# main1.net
KiCad netlist of a schematic drawn in EAGLE
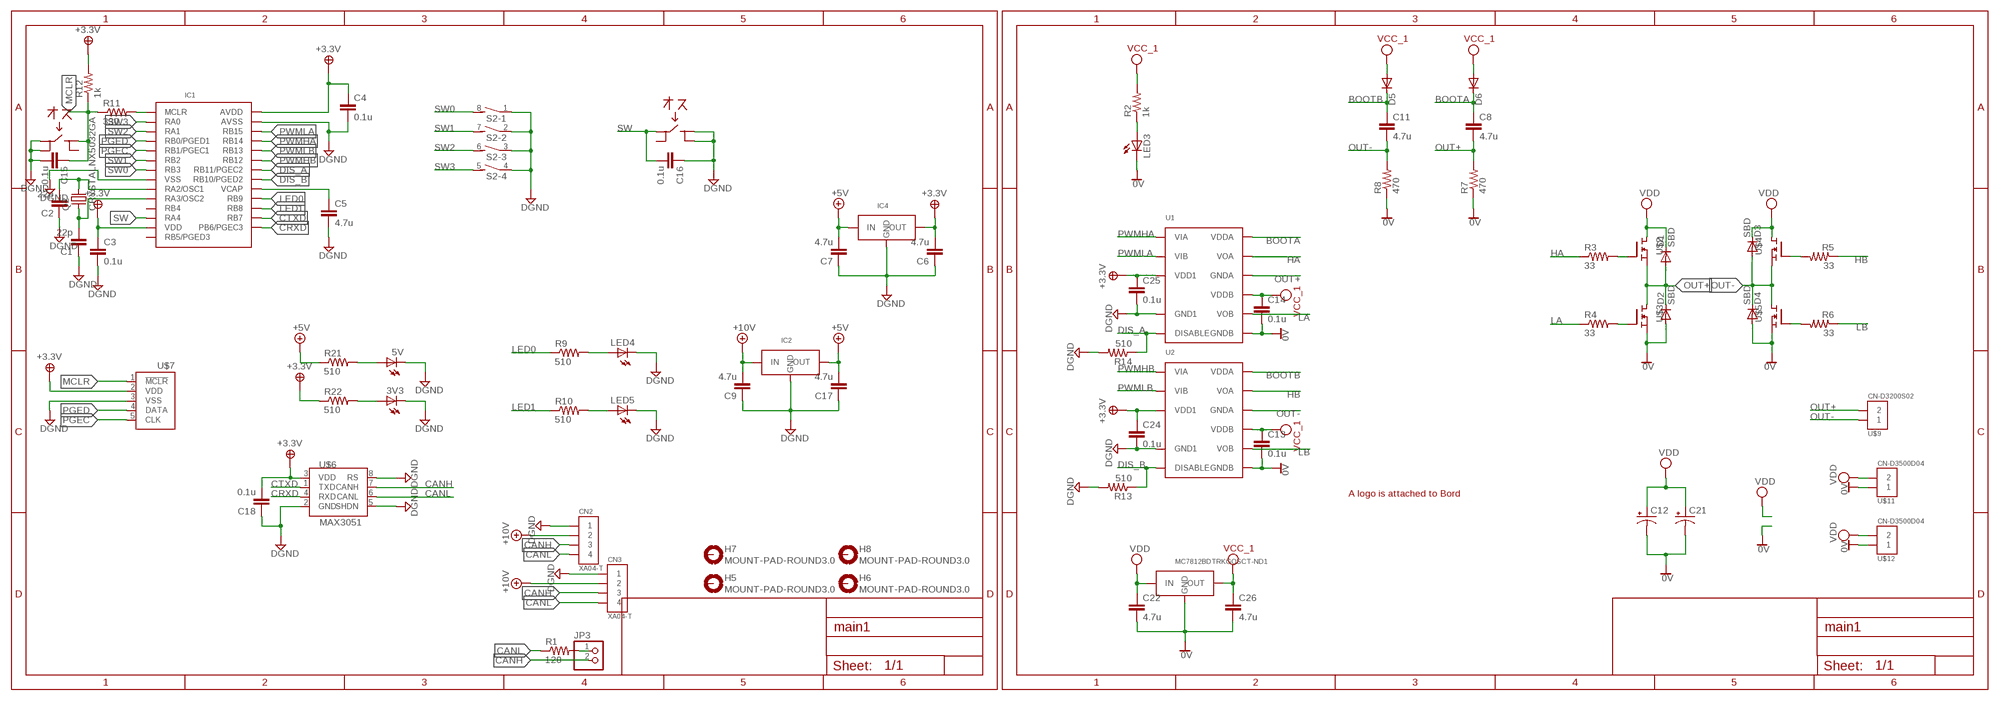
[diagram p0: schematic, sheet 1]

(export (version "E")
  (design (tool "Eeschema 10.0.6"))
  (components
    (comp (ref "3V3")
      (value "LEDCHIPLED_0805")
      (footprint "eagle-import:CHIPLED_0805")
      (libsource (lib "eagle-import") (part "LEDCHIPLED_0805"))
    )
    (comp (ref "5V")
      (value "LEDCHIPLED_0805")
      (footprint "eagle-import:CHIPLED_0805")
      (libsource (lib "eagle-import") (part "LEDCHIPLED_0805"))
    )
    (comp (ref "C1")
      (value "22p")
      (footprint "eagle-import:C0603K")
      (libsource (lib "eagle-import") (part "C-EUC0603K"))
    )
    (comp (ref "C2")
      (value "22p")
      (footprint "eagle-import:C0603K")
      (libsource (lib "eagle-import") (part "C-EUC0603K"))
    )
    (comp (ref "C3")
      (value "0.1u")
      (footprint "eagle-import:C0805K")
      (libsource (lib "eagle-import") (part "C-EUC0805K"))
    )
    (comp (ref "C4")
      (value "0.1u")
      (footprint "eagle-import:C0805K")
      (libsource (lib "eagle-import") (part "C-EUC0805K"))
    )
    (comp (ref "C5")
      (value "4.7u")
      (footprint "eagle-import:C0805K")
      (libsource (lib "eagle-import") (part "C-EUC0805K"))
    )
    (comp (ref "C6")
      (value "4.7u")
      (footprint "eagle-import:C0805K")
      (libsource (lib "eagle-import") (part "C-EUC0805K"))
    )
    (comp (ref "C7")
      (value "4.7u")
      (footprint "eagle-import:C0805K")
      (libsource (lib "eagle-import") (part "C-EUC0805K"))
    )
    (comp (ref "C8")
      (value "4.7u")
      (footprint "eagle-import:C0805K")
      (libsource (lib "eagle-import") (part "C-EUC0805K"))
    )
    (comp (ref "C9")
      (value "4.7u")
      (footprint "eagle-import:C0805K")
      (libsource (lib "eagle-import") (part "C-EUC0805K"))
    )
    (comp (ref "C11")
      (value "4.7u")
      (footprint "eagle-import:C0805K")
      (libsource (lib "eagle-import") (part "C-EUC0805K"))
    )
    (comp (ref "C12")
      (value "CPOL-USG")
      (footprint "eagle-import:PANASONIC_G")
      (libsource (lib "eagle-import") (part "CPOL-USG"))
    )
    (comp (ref "C13")
      (value "0.1u")
      (footprint "eagle-import:C0805K")
      (libsource (lib "eagle-import") (part "C-EUC0805K"))
    )
    (comp (ref "C14")
      (value "0.1u")
      (footprint "eagle-import:C0805K")
      (libsource (lib "eagle-import") (part "C-EUC0805K"))
    )
    (comp (ref "C15")
      (value "0.1u")
      (footprint "eagle-import:C0603K")
      (libsource (lib "eagle-import") (part "C-EUC0603K"))
    )
    (comp (ref "C16")
      (value "0.1u")
      (footprint "eagle-import:C0603K")
      (libsource (lib "eagle-import") (part "C-EUC0603K"))
    )
    (comp (ref "C17")
      (value "4.7u")
      (footprint "eagle-import:C0805K")
      (libsource (lib "eagle-import") (part "C-EUC0805K"))
    )
    (comp (ref "C18")
      (value "0.1u")
      (footprint "eagle-import:C0603K")
      (libsource (lib "eagle-import") (part "C-EUC0603K"))
    )
    (comp (ref "C21")
      (value "CPOL-USG")
      (footprint "eagle-import:PANASONIC_G")
      (libsource (lib "eagle-import") (part "CPOL-USG"))
    )
    (comp (ref "C22")
      (value "4.7u")
      (footprint "eagle-import:C0805K")
      (libsource (lib "eagle-import") (part "C-EUC0805K"))
    )
    (comp (ref "C24")
      (value "0.1u")
      (footprint "eagle-import:C0805K")
      (libsource (lib "eagle-import") (part "C-EUC0805K"))
    )
    (comp (ref "C25")
      (value "0.1u")
      (footprint "eagle-import:C0805K")
      (libsource (lib "eagle-import") (part "C-EUC0805K"))
    )
    (comp (ref "C26")
      (value "4.7u")
      (footprint "eagle-import:C0805K")
      (libsource (lib "eagle-import") (part "C-EUC0805K"))
    )
    (comp (ref "CN2")
      (value "XA04-T")
      (footprint "eagle-import:XA04")
      (libsource (lib "eagle-import") (part "XA04-T"))
    )
    (comp (ref "CN3")
      (value "XA04-T")
      (footprint "eagle-import:XA04")
      (libsource (lib "eagle-import") (part "XA04-T"))
    )
    (comp (ref "D1")
      (value "SBD")
      (footprint "eagle-import:SOD106-R")
      (libsource (lib "eagle-import") (part "DIODE-SOD106-R"))
    )
    (comp (ref "D2")
      (value "SBD")
      (footprint "eagle-import:SOD106-R")
      (libsource (lib "eagle-import") (part "DIODE-SOD106-R"))
    )
    (comp (ref "D3")
      (value "SBD")
      (footprint "eagle-import:SOD106-R")
      (libsource (lib "eagle-import") (part "DIODE-SOD106-R"))
    )
    (comp (ref "D4")
      (value "SBD")
      (footprint "eagle-import:SOD106-R")
      (libsource (lib "eagle-import") (part "DIODE-SOD106-R"))
    )
    (comp (ref "D5")
      (value "DIODE-SOD106-R")
      (footprint "eagle-import:SOD106-R")
      (libsource (lib "eagle-import") (part "DIODE-SOD106-R"))
    )
    (comp (ref "D6")
      (value "DIODE-SOD106-R")
      (footprint "eagle-import:SOD106-R")
      (libsource (lib "eagle-import") (part "DIODE-SOD106-R"))
    )
    (comp (ref "H5")
      (value "MOUNT-PAD-ROUND3.0")
      (footprint "eagle-import:3,0-PAD")
      (libsource (lib "eagle-import") (part "MOUNT-PAD-ROUND3.0"))
    )
    (comp (ref "H6")
      (value "MOUNT-PAD-ROUND3.0")
      (footprint "eagle-import:3,0-PAD")
      (libsource (lib "eagle-import") (part "MOUNT-PAD-ROUND3.0"))
    )
    (comp (ref "H7")
      (value "MOUNT-PAD-ROUND3.0")
      (footprint "eagle-import:3,0-PAD")
      (libsource (lib "eagle-import") (part "MOUNT-PAD-ROUND3.0"))
    )
    (comp (ref "H8")
      (value "MOUNT-PAD-ROUND3.0")
      (footprint "eagle-import:3,0-PAD")
      (libsource (lib "eagle-import") (part "MOUNT-PAD-ROUND3.0"))
    )
    (comp (ref "IC1")
      (value "DSPIC33FJ32MC302/64MC202/64MC802/128MC202/128MC802")
      (footprint "eagle-import:SOIC28")
      (libsource (lib "eagle-import") (part "DSPIC33FJ32MC302/64MC202/64MC802/128MC202/128MC802"))
    )
    (comp (ref "IC2")
      (value "REGULATERNJM2845DL1")
      (footprint "eagle-import:TO-252-2")
      (libsource (lib "eagle-import") (part "REGULATERNJM2845DL1"))
    )
    (comp (ref "IC4")
      (value "REGULATERAZ1117CR")
      (footprint "eagle-import:SOT89")
      (libsource (lib "eagle-import") (part "REGULATERAZ1117CR"))
    )
    (comp (ref "JP3")
      (value "PINHD-1X02_2.54")
      (footprint "eagle-import:1X02")
      (libsource (lib "eagle-import") (part "PINHD-1X02_2.54"))
    )
    (comp (ref "LED3")
      (value "LEDCHIPLED_0805")
      (footprint "eagle-import:CHIPLED_0805")
      (libsource (lib "eagle-import") (part "LEDCHIPLED_0805"))
    )
    (comp (ref "LED4")
      (value "LEDCHIPLED_0805")
      (footprint "eagle-import:CHIPLED_0805")
      (libsource (lib "eagle-import") (part "LEDCHIPLED_0805"))
    )
    (comp (ref "LED5")
      (value "LEDCHIPLED_0805")
      (footprint "eagle-import:CHIPLED_0805")
      (libsource (lib "eagle-import") (part "LEDCHIPLED_0805"))
    )
    (comp (ref "MC7812BDTRKGOSCT-ND1")
      (value "REGULATERMIC2940A-5.0WU")
      (footprint "eagle-import:TO-263-3")
      (libsource (lib "eagle-import") (part "REGULATERMIC2940A-5.0WU"))
    )
    (comp (ref "Q2")
      (value "CRYSTALNX5032GA")
      (footprint "eagle-import:NX5032GA")
      (libsource (lib "eagle-import") (part "CRYSTALNX5032GA"))
    )
    (comp (ref "R1")
      (value "120")
      (footprint "eagle-import:R0805")
      (libsource (lib "eagle-import") (part "R-US_R0805"))
    )
    (comp (ref "R2")
      (value "1k")
      (footprint "eagle-import:R0603")
      (libsource (lib "eagle-import") (part "R-US_R0603"))
    )
    (comp (ref "R3")
      (value "33")
      (footprint "eagle-import:R2512")
      (libsource (lib "eagle-import") (part "R-US_R2512"))
    )
    (comp (ref "R4")
      (value "33")
      (footprint "eagle-import:R2512")
      (libsource (lib "eagle-import") (part "R-US_R2512"))
    )
    (comp (ref "R5")
      (value "33")
      (footprint "eagle-import:R2512")
      (libsource (lib "eagle-import") (part "R-US_R2512"))
    )
    (comp (ref "R6")
      (value "33")
      (footprint "eagle-import:R2512")
      (libsource (lib "eagle-import") (part "R-US_R2512"))
    )
    (comp (ref "R7")
      (value "470")
      (footprint "eagle-import:R2512")
      (libsource (lib "eagle-import") (part "R-US_R2512"))
    )
    (comp (ref "R8")
      (value "470")
      (footprint "eagle-import:R2512")
      (libsource (lib "eagle-import") (part "R-US_R2512"))
    )
    (comp (ref "R9")
      (value "510")
      (footprint "eagle-import:R0603")
      (libsource (lib "eagle-import") (part "R-US_R0603"))
    )
    (comp (ref "R10")
      (value "510")
      (footprint "eagle-import:R0603")
      (libsource (lib "eagle-import") (part "R-US_R0603"))
    )
    (comp (ref "R11")
      (value "330")
      (footprint "eagle-import:R0603")
      (libsource (lib "eagle-import") (part "R-US_R0603"))
    )
    (comp (ref "R12")
      (value "1k")
      (footprint "eagle-import:R0603")
      (libsource (lib "eagle-import") (part "R-US_R0603"))
    )
    (comp (ref "R13")
      (value "510")
      (footprint "eagle-import:R0603")
      (libsource (lib "eagle-import") (part "R-US_R0603"))
    )
    (comp (ref "R14")
      (value "510")
      (footprint "eagle-import:R0603")
      (libsource (lib "eagle-import") (part "R-US_R0603"))
    )
    (comp (ref "R21")
      (value "510")
      (footprint "eagle-import:R0603")
      (libsource (lib "eagle-import") (part "R-US_R0603"))
    )
    (comp (ref "R22")
      (value "510")
      (footprint "eagle-import:R0603")
      (libsource (lib "eagle-import") (part "R-US_R0603"))
    )
    (comp (ref "S2")
      (value "DIP04S")
      (footprint "eagle-import:DIP04S")
      (libsource (lib "eagle-import") (part "DIP04S"))
    )
    (comp (ref "SW1")
      (value "SWITCH_4PALPS")
      (footprint "eagle-import:SKRP")
      (libsource (lib "eagle-import") (part "SWITCH_4PALPS"))
    )
    (comp (ref "SW2")
      (value "SWITCH_4PALPS")
      (footprint "eagle-import:SKRP")
      (libsource (lib "eagle-import") (part "SWITCH_4PALPS"))
    )
    (comp (ref "U$1")
      (value "CN-D3500D04")
      (footprint "eagle-import:D-3500D04")
      (libsource (lib "eagle-import") (part "CN-D3500D04"))
    )
    (comp (ref "U$2")
      (value "FET_NCHFDBL0065N40")
      (footprint "eagle-import:MO-299A")
      (libsource (lib "eagle-import") (part "FET_NCHFDBL0065N40"))
    )
    (comp (ref "U$3")
      (value "FET_NCHFDBL0065N40")
      (footprint "eagle-import:MO-299A")
      (libsource (lib "eagle-import") (part "FET_NCHFDBL0065N40"))
    )
    (comp (ref "U$4")
      (value "FET_NCHFDBL0065N40")
      (footprint "eagle-import:MO-299A")
      (libsource (lib "eagle-import") (part "FET_NCHFDBL0065N40"))
    )
    (comp (ref "U$5")
      (value "FET_NCHFDBL0065N40")
      (footprint "eagle-import:MO-299A")
      (libsource (lib "eagle-import") (part "FET_NCHFDBL0065N40"))
    )
    (comp (ref "U$6")
      (value "MAX3051")
      (footprint "eagle-import:SOIC8")
      (libsource (lib "eagle-import") (part "MAX3051"))
    )
    (comp (ref "U$7")
      (value "WRITE_FOR_PICT")
      (footprint "eagle-import:ZH05")
      (libsource (lib "eagle-import") (part "WRITE_FOR_PICT"))
    )
    (comp (ref "U$8")
      (value "LOGOGOCHIUSA-14MM")
      (footprint "eagle-import:LOGO006")
      (libsource (lib "eagle-import") (part "LOGOGOCHIUSA-14MM"))
    )
    (comp (ref "U$9")
      (value "CN-D3200S02")
      (footprint "eagle-import:D-3200S02-S")
      (libsource (lib "eagle-import") (part "CN-D3200S02"))
    )
    (comp (ref "U1")
      (value "ADUM3223_SMD")
      (footprint "eagle-import:SOIC16_N")
      (libsource (lib "eagle-import") (part "ADUM3223_SMD"))
    )
    (comp (ref "U2")
      (value "ADUM3223_SMD")
      (footprint "eagle-import:SOIC16_N")
      (libsource (lib "eagle-import") (part "ADUM3223_SMD"))
    )
  )
  (nets
    (net (code "1") (name "+3.3V") (class "Default")
      (node (ref "C18") (pin "2") (pinfunction "2_2") (pintype "passive"))
      (node (ref "C24") (pin "1") (pinfunction "1_1") (pintype "passive"))
      (node (ref "C25") (pin "1") (pinfunction "1_1") (pintype "passive"))
      (node (ref "C3") (pin "1") (pinfunction "1_1") (pintype "passive"))
      (node (ref "C4") (pin "1") (pinfunction "1_1") (pintype "passive"))
      (node (ref "C6") (pin "2") (pinfunction "2_2") (pintype "passive"))
      (node (ref "IC1") (pin "13") (pinfunction "VDD_13") (pintype "bidirectional"))
      (node (ref "IC1") (pin "28") (pinfunction "AVDD_28") (pintype "bidirectional"))
      (node (ref "IC4") (pin "2") (pinfunction "OUT_2") (pintype "bidirectional"))
      (node (ref "IC4") (pin "P") (pinfunction "OUT_P") (pintype "bidirectional"))
      (node (ref "R12") (pin "2") (pinfunction "2_2") (pintype "passive"))
      (node (ref "R22") (pin "1") (pinfunction "1_1") (pintype "passive"))
      (node (ref "U$6") (pin "3") (pinfunction "VDD_3") (pintype "bidirectional"))
      (node (ref "U$7") (pin "2") (pinfunction "VDD_2") (pintype "bidirectional"))
      (node (ref "U1") (pin "P$3") (pinfunction "VDD1_P$3") (pintype "bidirectional"))
      (node (ref "U1") (pin "P$8") (pinfunction "VDD1_P$8") (pintype "bidirectional"))
      (node (ref "U2") (pin "P$3") (pinfunction "VDD1_P$3") (pintype "bidirectional"))
      (node (ref "U2") (pin "P$8") (pinfunction "VDD1_P$8") (pintype "bidirectional"))
    )
    (net (code "2") (name "+5V") (class "Default")
      (node (ref "C17") (pin "2") (pinfunction "2_2") (pintype "passive"))
      (node (ref "C7") (pin "2") (pinfunction "2_2") (pintype "passive"))
      (node (ref "IC2") (pin "3") (pinfunction "OUT_3") (pintype "bidirectional"))
      (node (ref "IC4") (pin "3") (pinfunction "IN_3") (pintype "bidirectional"))
      (node (ref "R21") (pin "1") (pinfunction "1_1") (pintype "passive"))
    )
    (net (code "3") (name "+10V") (class "Default")
      (node (ref "C9") (pin "2") (pinfunction "2_2") (pintype "passive"))
      (node (ref "CN2") (pin "PIN2") (pinfunction "2_PIN2") (pintype "bidirectional"))
      (node (ref "CN3") (pin "PIN2") (pinfunction "2_PIN2") (pintype "bidirectional"))
      (node (ref "IC2") (pin "1") (pinfunction "IN_1") (pintype "bidirectional"))
    )
    (net (code "4") (name "/BOOTA") (class "Default")
      (node (ref "C8") (pin "1") (pinfunction "1_1") (pintype "passive"))
      (node (ref "D6") (pin "C") (pinfunction "C_C") (pintype "passive"))
      (node (ref "U1") (pin "P$16") (pinfunction "VDDA_P$16") (pintype "bidirectional"))
    )
    (net (code "5") (name "/BOOTB") (class "Default")
      (node (ref "C11") (pin "1") (pinfunction "1_1") (pintype "passive"))
      (node (ref "D5") (pin "C") (pinfunction "C_C") (pintype "passive"))
      (node (ref "U2") (pin "P$16") (pinfunction "VDDA_P$16") (pintype "bidirectional"))
    )
    (net (code "6") (name "/HA") (class "Default")
      (node (ref "R3") (pin "1") (pinfunction "1_1") (pintype "passive"))
      (node (ref "U1") (pin "P$15") (pinfunction "VOA_P$15") (pintype "bidirectional"))
    )
    (net (code "7") (name "/HB") (class "Default")
      (node (ref "R5") (pin "1") (pinfunction "1_1") (pintype "passive"))
      (node (ref "U2") (pin "P$15") (pinfunction "VOA_P$15") (pintype "bidirectional"))
    )
    (net (code "8") (name "/LA") (class "Default")
      (node (ref "R4") (pin "1") (pinfunction "1_1") (pintype "passive"))
      (node (ref "U1") (pin "P$10") (pinfunction "VOB_P$10") (pintype "bidirectional"))
    )
    (net (code "9") (name "/LB") (class "Default")
      (node (ref "R6") (pin "1") (pinfunction "1_1") (pintype "passive"))
      (node (ref "U2") (pin "P$10") (pinfunction "VOB_P$10") (pintype "bidirectional"))
    )
    (net (code "10") (name "0V") (class "Default")
      (node (ref "C12") (pin "-") (pinfunction "-_-") (pintype "passive"))
      (node (ref "C13") (pin "2") (pinfunction "2_2") (pintype "passive"))
      (node (ref "C14") (pin "2") (pinfunction "2_2") (pintype "passive"))
      (node (ref "C21") (pin "-") (pinfunction "-_-") (pintype "passive"))
      (node (ref "C22") (pin "2") (pinfunction "2_2") (pintype "passive"))
      (node (ref "C26") (pin "2") (pinfunction "2_2") (pintype "passive"))
      (node (ref "D2") (pin "A") (pinfunction "A_A") (pintype "passive"))
      (node (ref "D4") (pin "A") (pinfunction "A_A") (pintype "passive"))
      (node (ref "LED3") (pin "C") (pinfunction "C_C") (pintype "passive"))
      (node (ref "MC7812BDTRKGOSCT-ND1") (pin "2") (pinfunction "GND_2") (pintype "bidirectional"))
      (node (ref "MC7812BDTRKGOSCT-ND1") (pin "4") (pinfunction "GND_4") (pintype "bidirectional"))
      (node (ref "R7") (pin "1") (pinfunction "1_1") (pintype "passive"))
      (node (ref "R8") (pin "1") (pinfunction "1_1") (pintype "passive"))
      (node (ref "U$1") (pin "01A") (pinfunction "1_01A") (pintype "bidirectional"))
      (node (ref "U$1") (pin "02A") (pinfunction "1_02A") (pintype "bidirectional"))
      (node (ref "U$3") (pin "2") (pinfunction "S_2") (pintype "bidirectional"))
      (node (ref "U$3") (pin "3") (pinfunction "S_3") (pintype "bidirectional"))
      (node (ref "U$3") (pin "4") (pinfunction "S_4") (pintype "bidirectional"))
      (node (ref "U$3") (pin "5") (pinfunction "S_5") (pintype "bidirectional"))
      (node (ref "U$3") (pin "6") (pinfunction "S_6") (pintype "bidirectional"))
      (node (ref "U$3") (pin "7") (pinfunction "S_7") (pintype "bidirectional"))
      (node (ref "U$3") (pin "8") (pinfunction "S_8") (pintype "bidirectional"))
      (node (ref "U$5") (pin "2") (pinfunction "S_2") (pintype "bidirectional"))
      (node (ref "U$5") (pin "3") (pinfunction "S_3") (pintype "bidirectional"))
      (node (ref "U$5") (pin "4") (pinfunction "S_4") (pintype "bidirectional"))
      (node (ref "U$5") (pin "5") (pinfunction "S_5") (pintype "bidirectional"))
      (node (ref "U$5") (pin "6") (pinfunction "S_6") (pintype "bidirectional"))
      (node (ref "U$5") (pin "7") (pinfunction "S_7") (pintype "bidirectional"))
      (node (ref "U$5") (pin "8") (pinfunction "S_8") (pintype "bidirectional"))
      (node (ref "U1") (pin "P$9") (pinfunction "GNDB_P$9") (pintype "bidirectional"))
      (node (ref "U2") (pin "P$9") (pinfunction "GNDB_P$9") (pintype "bidirectional"))
    )
    (net (code "11") (name "CANH") (class "Default")
      (node (ref "CN2") (pin "PIN3") (pinfunction "3_PIN3") (pintype "bidirectional"))
      (node (ref "CN3") (pin "PIN3") (pinfunction "3_PIN3") (pintype "bidirectional"))
      (node (ref "JP3") (pin "2") (pinfunction "2_2") (pintype "passive"))
      (node (ref "U$6") (pin "7") (pinfunction "CANH_7") (pintype "bidirectional"))
    )
    (net (code "12") (name "CANL") (class "Default")
      (node (ref "CN2") (pin "PIN4") (pinfunction "4_PIN4") (pintype "bidirectional"))
      (node (ref "CN3") (pin "PIN4") (pinfunction "4_PIN4") (pintype "bidirectional"))
      (node (ref "R1") (pin "1") (pinfunction "1_1") (pintype "passive"))
      (node (ref "U$6") (pin "6") (pinfunction "CANL_6") (pintype "bidirectional"))
    )
    (net (code "13") (name "CRXD") (class "Default")
      (node (ref "IC1") (pin "15") (pinfunction "PB6/PGEC3_15") (pintype "bidirectional"))
      (node (ref "U$6") (pin "4") (pinfunction "RXD_4") (pintype "bidirectional"))
    )
    (net (code "14") (name "CTXD") (class "Default")
      (node (ref "IC1") (pin "16") (pinfunction "RB7_16") (pintype "bidirectional"))
      (node (ref "U$6") (pin "1") (pinfunction "TXD_1") (pintype "bidirectional"))
    )
    (net (code "15") (name "DGND") (class "Default")
      (node (ref "3V3") (pin "C") (pinfunction "C_C") (pintype "passive"))
      (node (ref "5V") (pin "C") (pinfunction "C_C") (pintype "passive"))
      (node (ref "C1") (pin "1") (pinfunction "1_1") (pintype "passive"))
      (node (ref "C15") (pin "2") (pinfunction "2_2") (pintype "passive"))
      (node (ref "C16") (pin "1") (pinfunction "1_1") (pintype "passive"))
      (node (ref "C17") (pin "1") (pinfunction "1_1") (pintype "passive"))
      (node (ref "C18") (pin "1") (pinfunction "1_1") (pintype "passive"))
      (node (ref "C2") (pin "1") (pinfunction "1_1") (pintype "passive"))
      (node (ref "C24") (pin "2") (pinfunction "2_2") (pintype "passive"))
      (node (ref "C25") (pin "2") (pinfunction "2_2") (pintype "passive"))
      (node (ref "C3") (pin "2") (pinfunction "2_2") (pintype "passive"))
      (node (ref "C4") (pin "2") (pinfunction "2_2") (pintype "passive"))
      (node (ref "C5") (pin "2") (pinfunction "2_2") (pintype "passive"))
      (node (ref "C6") (pin "1") (pinfunction "1_1") (pintype "passive"))
      (node (ref "C7") (pin "1") (pinfunction "1_1") (pintype "passive"))
      (node (ref "C9") (pin "1") (pinfunction "1_1") (pintype "passive"))
      (node (ref "CN2") (pin "PIN1") (pinfunction "1_PIN1") (pintype "bidirectional"))
      (node (ref "CN3") (pin "PIN1") (pinfunction "1_PIN1") (pintype "bidirectional"))
      (node (ref "IC1") (pin "19") (pinfunction "VSS_19") (pintype "bidirectional"))
      (node (ref "IC1") (pin "27") (pinfunction "AVSS_27") (pintype "bidirectional"))
      (node (ref "IC1") (pin "8") (pinfunction "VSS_8") (pintype "bidirectional"))
      (node (ref "IC2") (pin "2") (pinfunction "GND_2") (pintype "bidirectional"))
      (node (ref "IC4") (pin "1") (pinfunction "GND_1") (pintype "bidirectional"))
      (node (ref "LED4") (pin "C") (pinfunction "C_C") (pintype "passive"))
      (node (ref "LED5") (pin "C") (pinfunction "C_C") (pintype "passive"))
      (node (ref "R13") (pin "2") (pinfunction "2_2") (pintype "passive"))
      (node (ref "R14") (pin "2") (pinfunction "2_2") (pintype "passive"))
      (node (ref "S2") (pin "1") (pinfunction "1_1") (pintype "passive"))
      (node (ref "S2") (pin "2") (pinfunction "1_2") (pintype "passive"))
      (node (ref "S2") (pin "3") (pinfunction "1_3") (pintype "passive"))
      (node (ref "S2") (pin "4") (pinfunction "1_4") (pintype "passive"))
      (node (ref "SW1") (pin "1") (pinfunction "1_1") (pintype "bidirectional"))
      (node (ref "SW1") (pin "2") (pinfunction "2_2") (pintype "bidirectional"))
      (node (ref "SW2") (pin "3") (pinfunction "3_3") (pintype "bidirectional"))
      (node (ref "SW2") (pin "4") (pinfunction "4_4") (pintype "bidirectional"))
      (node (ref "U$6") (pin "2") (pinfunction "GND_2") (pintype "bidirectional"))
      (node (ref "U$6") (pin "5") (pinfunction "SHDN_5") (pintype "bidirectional"))
      (node (ref "U$6") (pin "8") (pinfunction "RS_8") (pintype "bidirectional"))
      (node (ref "U$7") (pin "3") (pinfunction "VSS_3") (pintype "bidirectional"))
      (node (ref "U1") (pin "P$4") (pinfunction "GND1_P$4") (pintype "bidirectional"))
      (node (ref "U2") (pin "P$4") (pinfunction "GND1_P$4") (pintype "bidirectional"))
    )
    (net (code "16") (name "DIS_A") (class "Default")
      (node (ref "IC1") (pin "22") (pinfunction "RB11/PGEC2_22") (pintype "bidirectional"))
      (node (ref "R14") (pin "1") (pinfunction "1_1") (pintype "passive"))
      (node (ref "U1") (pin "P$5") (pinfunction "DISABLE_P$5") (pintype "bidirectional"))
    )
    (net (code "17") (name "DIS_B") (class "Default")
      (node (ref "IC1") (pin "21") (pinfunction "RB10/PGED2_21") (pintype "bidirectional"))
      (node (ref "R13") (pin "1") (pinfunction "1_1") (pintype "passive"))
      (node (ref "U2") (pin "P$5") (pinfunction "DISABLE_P$5") (pintype "bidirectional"))
    )
    (net (code "18") (name "LED0") (class "Default")
      (node (ref "IC1") (pin "18") (pinfunction "RB9_18") (pintype "bidirectional"))
      (node (ref "R9") (pin "1") (pinfunction "1_1") (pintype "passive"))
    )
    (net (code "19") (name "LED1") (class "Default")
      (node (ref "IC1") (pin "17") (pinfunction "RB8_17") (pintype "bidirectional"))
      (node (ref "R10") (pin "1") (pinfunction "1_1") (pintype "passive"))
    )
    (net (code "20") (name "MCLR") (class "Default")
      (node (ref "C15") (pin "1") (pinfunction "1_1") (pintype "passive"))
      (node (ref "R11") (pin "1") (pinfunction "1_1") (pintype "passive"))
      (node (ref "R12") (pin "1") (pinfunction "1_1") (pintype "passive"))
      (node (ref "SW1") (pin "3") (pinfunction "3_3") (pintype "bidirectional"))
      (node (ref "U$7") (pin "1") (pinfunction "~{MCLR}_1") (pintype "bidirectional"))
    )
    (net (code "21") (name "Net-(3V3-PadA)") (class "Default")
      (node (ref "3V3") (pin "A") (pinfunction "A_A") (pintype "passive"))
      (node (ref "R22") (pin "2") (pinfunction "2_2") (pintype "passive"))
    )
    (net (code "22") (name "Net-(5V-PadA)") (class "Default")
      (node (ref "5V") (pin "A") (pinfunction "A_A") (pintype "passive"))
      (node (ref "R21") (pin "2") (pinfunction "2_2") (pintype "passive"))
    )
    (net (code "23") (name "Net-(IC1-MCLR)") (class "Default")
      (node (ref "IC1") (pin "1") (pinfunction "MCLR_1") (pintype "bidirectional"))
      (node (ref "R11") (pin "2") (pinfunction "2_2") (pintype "passive"))
    )
    (net (code "24") (name "Net-(IC1-RA2{slash}OSC1)") (class "Default")
      (node (ref "C2") (pin "2") (pinfunction "2_2") (pintype "passive"))
      (node (ref "IC1") (pin "9") (pinfunction "RA2/OSC1_9") (pintype "bidirectional"))
      (node (ref "Q2") (pin "2") (pinfunction "2_2") (pintype "bidirectional"))
    )
    (net (code "25") (name "Net-(IC1-RA3{slash}OSC2)") (class "Default")
      (node (ref "C1") (pin "2") (pinfunction "2_2") (pintype "passive"))
      (node (ref "IC1") (pin "10") (pinfunction "RA3/OSC2_10") (pintype "bidirectional"))
      (node (ref "Q2") (pin "1") (pinfunction "1_1") (pintype "bidirectional"))
    )
    (net (code "26") (name "Net-(IC1-VCAP)") (class "Default")
      (node (ref "C5") (pin "1") (pinfunction "1_1") (pintype "passive"))
      (node (ref "IC1") (pin "20") (pinfunction "VCAP_20") (pintype "bidirectional"))
    )
    (net (code "27") (name "Net-(JP3-Pad1)") (class "Default")
      (node (ref "JP3") (pin "1") (pinfunction "1_1") (pintype "passive"))
      (node (ref "R1") (pin "2") (pinfunction "2_2") (pintype "passive"))
    )
    (net (code "28") (name "Net-(LED3-PadA)") (class "Default")
      (node (ref "LED3") (pin "A") (pinfunction "A_A") (pintype "passive"))
      (node (ref "R2") (pin "1") (pinfunction "1_1") (pintype "passive"))
    )
    (net (code "29") (name "Net-(LED4-PadA)") (class "Default")
      (node (ref "LED4") (pin "A") (pinfunction "A_A") (pintype "passive"))
      (node (ref "R9") (pin "2") (pinfunction "2_2") (pintype "passive"))
    )
    (net (code "30") (name "Net-(LED5-PadA)") (class "Default")
      (node (ref "LED5") (pin "A") (pinfunction "A_A") (pintype "passive"))
      (node (ref "R10") (pin "2") (pinfunction "2_2") (pintype "passive"))
    )
    (net (code "31") (name "Net-(U$2-G)") (class "Default")
      (node (ref "R3") (pin "2") (pinfunction "2_2") (pintype "passive"))
      (node (ref "U$2") (pin "1") (pinfunction "G_1") (pintype "bidirectional"))
    )
    (net (code "32") (name "Net-(U$3-G)") (class "Default")
      (node (ref "R4") (pin "2") (pinfunction "2_2") (pintype "passive"))
      (node (ref "U$3") (pin "1") (pinfunction "G_1") (pintype "bidirectional"))
    )
    (net (code "33") (name "Net-(U$4-G)") (class "Default")
      (node (ref "R5") (pin "2") (pinfunction "2_2") (pintype "passive"))
      (node (ref "U$4") (pin "1") (pinfunction "G_1") (pintype "bidirectional"))
    )
    (net (code "34") (name "Net-(U$5-G)") (class "Default")
      (node (ref "R6") (pin "2") (pinfunction "2_2") (pintype "passive"))
      (node (ref "U$5") (pin "1") (pinfunction "G_1") (pintype "bidirectional"))
    )
    (net (code "35") (name "OUT+") (class "Default")
      (node (ref "C8") (pin "2") (pinfunction "2_2") (pintype "passive"))
      (node (ref "D1") (pin "A") (pinfunction "A_A") (pintype "passive"))
      (node (ref "D2") (pin "C") (pinfunction "C_C") (pintype "passive"))
      (node (ref "R7") (pin "2") (pinfunction "2_2") (pintype "passive"))
      (node (ref "U$2") (pin "2") (pinfunction "S_2") (pintype "bidirectional"))
      (node (ref "U$2") (pin "3") (pinfunction "S_3") (pintype "bidirectional"))
      (node (ref "U$2") (pin "4") (pinfunction "S_4") (pintype "bidirectional"))
      (node (ref "U$2") (pin "5") (pinfunction "S_5") (pintype "bidirectional"))
      (node (ref "U$2") (pin "6") (pinfunction "S_6") (pintype "bidirectional"))
      (node (ref "U$2") (pin "7") (pinfunction "S_7") (pintype "bidirectional"))
      (node (ref "U$2") (pin "8") (pinfunction "S_8") (pintype "bidirectional"))
      (node (ref "U$3") (pin "PAD1") (pinfunction "D_PAD1") (pintype "bidirectional"))
      (node (ref "U$3") (pin "PAD2") (pinfunction "D_PAD2") (pintype "bidirectional"))
      (node (ref "U$3") (pin "PAD3") (pinfunction "D_PAD3") (pintype "bidirectional"))
      (node (ref "U$3") (pin "PAD4") (pinfunction "D_PAD4") (pintype "bidirectional"))
      (node (ref "U$9") (pin "2") (pinfunction "2_2") (pintype "bidirectional"))
      (node (ref "U$9") (pin "P$2") (pinfunction "2_P$2") (pintype "bidirectional"))
      (node (ref "U1") (pin "P$14") (pinfunction "GNDA_P$14") (pintype "bidirectional"))
    )
    (net (code "36") (name "OUT-") (class "Default")
      (node (ref "C11") (pin "2") (pinfunction "2_2") (pintype "passive"))
      (node (ref "D3") (pin "A") (pinfunction "A_A") (pintype "passive"))
      (node (ref "D4") (pin "C") (pinfunction "C_C") (pintype "passive"))
      (node (ref "R8") (pin "2") (pinfunction "2_2") (pintype "passive"))
      (node (ref "U$4") (pin "2") (pinfunction "S_2") (pintype "bidirectional"))
      (node (ref "U$4") (pin "3") (pinfunction "S_3") (pintype "bidirectional"))
      (node (ref "U$4") (pin "4") (pinfunction "S_4") (pintype "bidirectional"))
      (node (ref "U$4") (pin "5") (pinfunction "S_5") (pintype "bidirectional"))
      (node (ref "U$4") (pin "6") (pinfunction "S_6") (pintype "bidirectional"))
      (node (ref "U$4") (pin "7") (pinfunction "S_7") (pintype "bidirectional"))
      (node (ref "U$4") (pin "8") (pinfunction "S_8") (pintype "bidirectional"))
      (node (ref "U$5") (pin "PAD1") (pinfunction "D_PAD1") (pintype "bidirectional"))
      (node (ref "U$5") (pin "PAD2") (pinfunction "D_PAD2") (pintype "bidirectional"))
      (node (ref "U$5") (pin "PAD3") (pinfunction "D_PAD3") (pintype "bidirectional"))
      (node (ref "U$5") (pin "PAD4") (pinfunction "D_PAD4") (pintype "bidirectional"))
      (node (ref "U$9") (pin "1") (pinfunction "1_1") (pintype "bidirectional"))
      (node (ref "U$9") (pin "P$1") (pinfunction "1_P$1") (pintype "bidirectional"))
      (node (ref "U2") (pin "P$14") (pinfunction "GNDA_P$14") (pintype "bidirectional"))
    )
    (net (code "37") (name "PGEC") (class "Default")
      (node (ref "IC1") (pin "5") (pinfunction "RB1/PGEC1_5") (pintype "bidirectional"))
      (node (ref "U$7") (pin "5") (pinfunction "CLK_5") (pintype "bidirectional"))
    )
    (net (code "38") (name "PGED") (class "Default")
      (node (ref "IC1") (pin "4") (pinfunction "RB0/PGED1_4") (pintype "bidirectional"))
      (node (ref "U$7") (pin "4") (pinfunction "DATA_4") (pintype "bidirectional"))
    )
    (net (code "39") (name "PWMHA") (class "Default")
      (node (ref "IC1") (pin "25") (pinfunction "RB14_25") (pintype "bidirectional"))
      (node (ref "U1") (pin "P$1") (pinfunction "VIA_P$1") (pintype "bidirectional"))
    )
    (net (code "40") (name "PWMHB") (class "Default")
      (node (ref "IC1") (pin "23") (pinfunction "RB12_23") (pintype "bidirectional"))
      (node (ref "U2") (pin "P$1") (pinfunction "VIA_P$1") (pintype "bidirectional"))
    )
    (net (code "41") (name "PWMLA") (class "Default")
      (node (ref "IC1") (pin "26") (pinfunction "RB15_26") (pintype "bidirectional"))
      (node (ref "U1") (pin "P$2") (pinfunction "VIB_P$2") (pintype "bidirectional"))
    )
    (net (code "42") (name "PWMLB") (class "Default")
      (node (ref "IC1") (pin "24") (pinfunction "RB13_24") (pintype "bidirectional"))
      (node (ref "U2") (pin "P$2") (pinfunction "VIB_P$2") (pintype "bidirectional"))
    )
    (net (code "43") (name "SW") (class "Default")
      (node (ref "C16") (pin "2") (pinfunction "2_2") (pintype "passive"))
      (node (ref "IC1") (pin "12") (pinfunction "RA4_12") (pintype "bidirectional"))
      (node (ref "SW2") (pin "1") (pinfunction "1_1") (pintype "bidirectional"))
    )
    (net (code "44") (name "SW0") (class "Default")
      (node (ref "IC1") (pin "7") (pinfunction "RB3_7") (pintype "bidirectional"))
      (node (ref "S2") (pin "8") (pinfunction "2_8") (pintype "passive"))
    )
    (net (code "45") (name "SW1") (class "Default")
      (node (ref "IC1") (pin "6") (pinfunction "RB2_6") (pintype "bidirectional"))
      (node (ref "S2") (pin "7") (pinfunction "2_7") (pintype "passive"))
    )
    (net (code "46") (name "SW2") (class "Default")
      (node (ref "IC1") (pin "3") (pinfunction "RA1_3") (pintype "bidirectional"))
      (node (ref "S2") (pin "6") (pinfunction "2_6") (pintype "passive"))
    )
    (net (code "47") (name "SW3") (class "Default")
      (node (ref "IC1") (pin "2") (pinfunction "RA0_2") (pintype "bidirectional"))
      (node (ref "S2") (pin "5") (pinfunction "2_5") (pintype "passive"))
    )
    (net (code "48") (name "VCC_1") (class "Default")
      (node (ref "C13") (pin "1") (pinfunction "1_1") (pintype "passive"))
      (node (ref "C14") (pin "1") (pinfunction "1_1") (pintype "passive"))
      (node (ref "C26") (pin "1") (pinfunction "1_1") (pintype "passive"))
      (node (ref "D5") (pin "A") (pinfunction "A_A") (pintype "passive"))
      (node (ref "D6") (pin "A") (pinfunction "A_A") (pintype "passive"))
      (node (ref "MC7812BDTRKGOSCT-ND1") (pin "3") (pinfunction "OUT_3") (pintype "bidirectional"))
      (node (ref "R2") (pin "2") (pinfunction "2_2") (pintype "passive"))
      (node (ref "U1") (pin "P$11") (pinfunction "VDDB_P$11") (pintype "bidirectional"))
      (node (ref "U2") (pin "P$11") (pinfunction "VDDB_P$11") (pintype "bidirectional"))
    )
    (net (code "49") (name "VDD") (class "Default")
      (node (ref "C12") (pin "+") (pinfunction "+_+") (pintype "passive"))
      (node (ref "C21") (pin "+") (pinfunction "+_+") (pintype "passive"))
      (node (ref "C22") (pin "1") (pinfunction "1_1") (pintype "passive"))
      (node (ref "D1") (pin "C") (pinfunction "C_C") (pintype "passive"))
      (node (ref "D3") (pin "C") (pinfunction "C_C") (pintype "passive"))
      (node (ref "MC7812BDTRKGOSCT-ND1") (pin "1") (pinfunction "IN_1") (pintype "bidirectional"))
      (node (ref "U$1") (pin "01B") (pinfunction "2_01B") (pintype "bidirectional"))
      (node (ref "U$1") (pin "02B") (pinfunction "2_02B") (pintype "bidirectional"))
      (node (ref "U$2") (pin "PAD1") (pinfunction "D_PAD1") (pintype "bidirectional"))
      (node (ref "U$2") (pin "PAD2") (pinfunction "D_PAD2") (pintype "bidirectional"))
      (node (ref "U$2") (pin "PAD3") (pinfunction "D_PAD3") (pintype "bidirectional"))
      (node (ref "U$2") (pin "PAD4") (pinfunction "D_PAD4") (pintype "bidirectional"))
      (node (ref "U$4") (pin "PAD1") (pinfunction "D_PAD1") (pintype "bidirectional"))
      (node (ref "U$4") (pin "PAD2") (pinfunction "D_PAD2") (pintype "bidirectional"))
      (node (ref "U$4") (pin "PAD3") (pinfunction "D_PAD3") (pintype "bidirectional"))
      (node (ref "U$4") (pin "PAD4") (pinfunction "D_PAD4") (pintype "bidirectional"))
    )
    (net (code "50") (name "unconnected-(H5-MOUNT-PadB3,0)") (class "Default")
      (node (ref "H5") (pin "B3,0") (pinfunction "MOUNT_B3,0") (pintype "passive"))
    )
    (net (code "51") (name "unconnected-(H6-MOUNT-PadB3,0)") (class "Default")
      (node (ref "H6") (pin "B3,0") (pinfunction "MOUNT_B3,0") (pintype "passive"))
    )
    (net (code "52") (name "unconnected-(H7-MOUNT-PadB3,0)") (class "Default")
      (node (ref "H7") (pin "B3,0") (pinfunction "MOUNT_B3,0") (pintype "passive"))
    )
    (net (code "53") (name "unconnected-(H8-MOUNT-PadB3,0)") (class "Default")
      (node (ref "H8") (pin "B3,0") (pinfunction "MOUNT_B3,0") (pintype "passive"))
    )
    (net (code "54") (name "unconnected-(IC1-RB4-Pad11)") (class "Default")
      (node (ref "IC1") (pin "11") (pinfunction "RB4_11") (pintype "bidirectional"))
    )
    (net (code "55") (name "unconnected-(IC1-RB5{slash}PGED3-Pad14)") (class "Default")
      (node (ref "IC1") (pin "14") (pinfunction "RB5/PGED3_14") (pintype "bidirectional"))
    )
    (net (code "56") (name "unconnected-(SW1-Pad4)") (class "Default")
      (node (ref "SW1") (pin "4") (pinfunction "4_4") (pintype "bidirectional"))
    )
    (net (code "57") (name "unconnected-(SW2-Pad2)") (class "Default")
      (node (ref "SW2") (pin "2") (pinfunction "2_2") (pintype "bidirectional"))
    )
  )
)
